# OCP2PCIe-H-F-4.net
KiCad netlist of a schematic drawn in Altium Designer
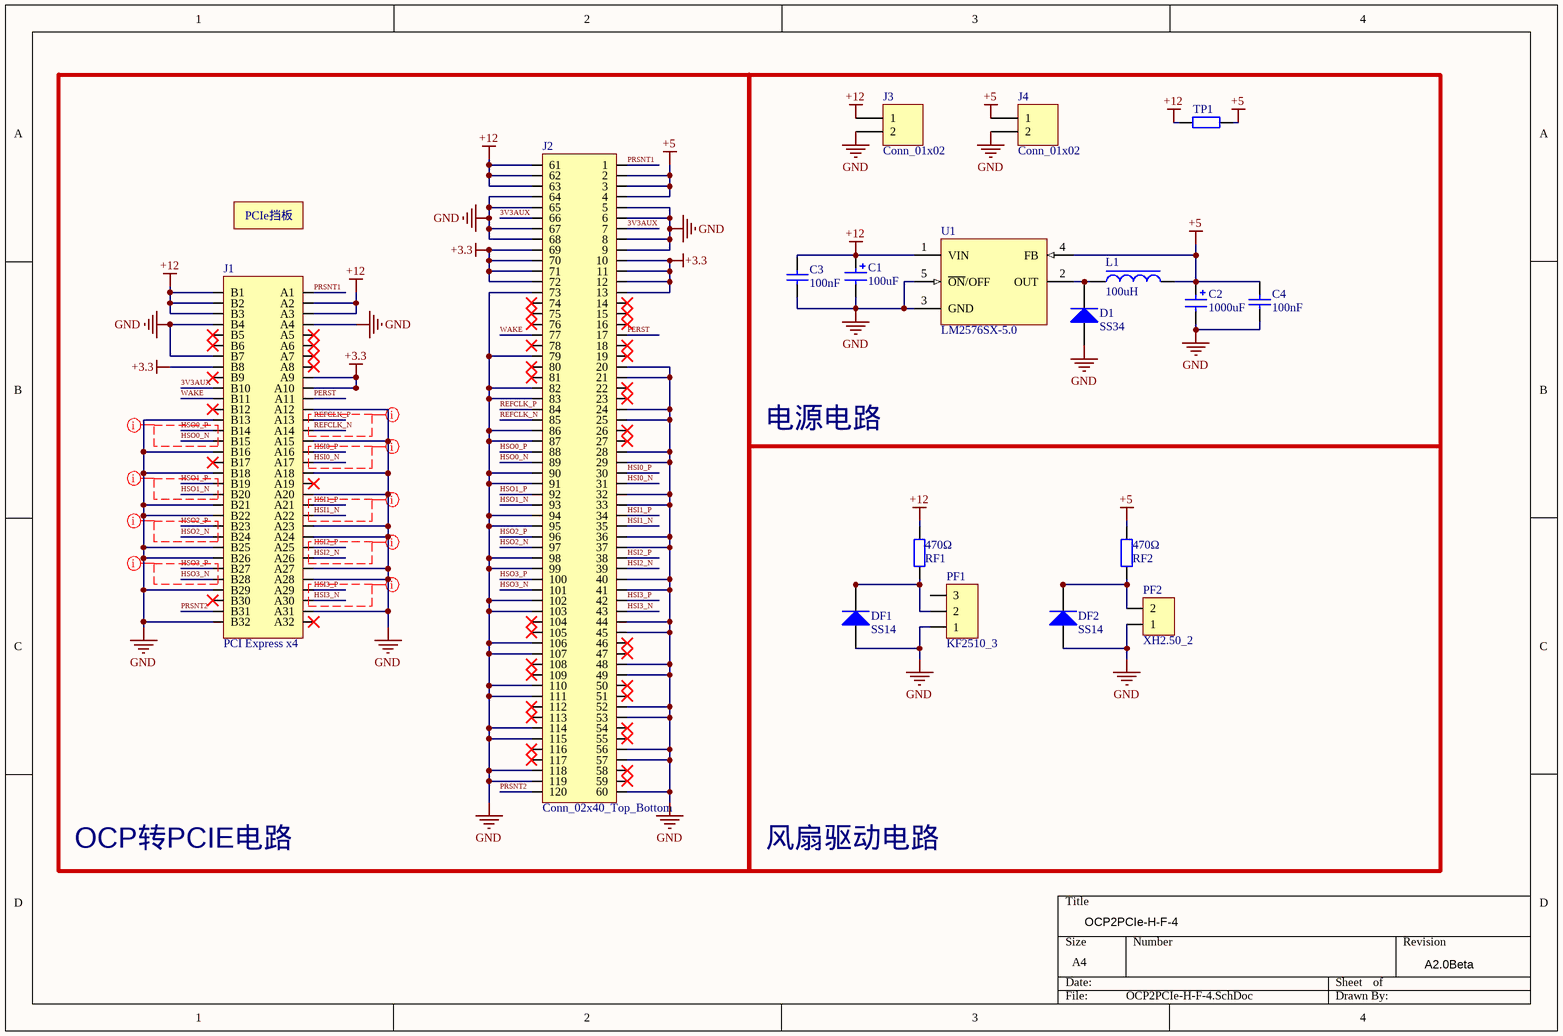
[diagram p0: OCP2PCIe-H-F-4.SchDoc]

(export (version "E")
  (design (tool "Eeschema 10.0.6"))
  (components
    (comp (ref "BEZEL")
      (value "BEZEL")
      (footprint "BEZEL")
      (description "PCIe挡板")
      (libsource (lib "OCP2PCIe-H-F-4") (part "BEZEL"))
    )
    (comp (ref "C1")
      (value "100uF")
      (footprint "CAP-SMD_BD5.0-L5.3-W5.3-FD")
      (description "贴片铝电解电容")
      (libsource (lib "OCP2PCIe") (part "7343_CP"))
    )
    (comp (ref "C2")
      (value "1000uF")
      (footprint "CAP-SMD_BD10.0-L10.3-W10.3-FD")
      (description "贴片铝电解电容")
      (libsource (lib "OCP2PCIe") (part "7343_CP"))
    )
    (comp (ref "C3")
      (value "100nF")
      (footprint "0603_C")
      (description "贴片电容")
      (libsource (lib "OCP2PCIe") (part "0805 Cap"))
    )
    (comp (ref "C4")
      (value "100nF")
      (footprint "0603_C")
      (description "贴片电容")
      (libsource (lib "OCP2PCIe") (part "0805 Cap"))
    )
    (comp (ref "D1")
      (value "SS34")
      (footprint "SMA(DO-214AC)_S1")
      (description "肖特基二极管")
      (libsource (lib "OCP2PCIe-H-F-4") (part "SMA(DO-214AC) M7"))
    )
    (comp (ref "DF1")
      (value "SS14")
      (footprint "SMA(DO-214AC)_S1")
      (description "二极管")
      (libsource (lib "OCP2PCIe-H-F-4") (part "SMA(DO-214AC) M7"))
    )
    (comp (ref "DF2")
      (value "SS14")
      (footprint "SMA(DO-214AC)_S1")
      (description "二极管")
      (libsource (lib "OCP2PCIe-H-F-4") (part "SMA(DO-214AC) M7"))
    )
    (comp (ref "J1")
      (value "PCI Express x4")
      (footprint "PCI Express x4")
      (description "插座-PCIe")
      (libsource (lib "OCP2PCIe") (part "PCI Express x4"))
    )
    (comp (ref "J2")
      (value "Conn_02x40_Top_Bottom")
      (footprint "Conn_02x40_Top_Bottom")
      (description "插座-0.8mm")
      (libsource (lib "OCP2PCIe") (part "Conn_02x40_Top_Bottom"))
    )
    (comp (ref "J3")
      (value "Conn_01x02")
      (footprint "Conn_01x02")
      (description "插座-2.54mm")
      (fields (field (name "PUBLISHER") "Altium Limited"))
      (libsource (lib "OCP2PCIe") (part "Conn_01x02"))
    )
    (comp (ref "J4")
      (value "Conn_01x02")
      (footprint "Conn_01x02")
      (description "插座-2.54mm")
      (fields (field (name "PUBLISHER") "Altium Limited"))
      (libsource (lib "OCP2PCIe") (part "Conn_01x02"))
    )
    (comp (ref "L1")
      (value "100uH")
      (footprint "SMD_5050")
      (description "贴片电感")
      (libsource (lib "OCP2PCIe-H-F-4") (part "SDM_Inductors"))
    )
    (comp (ref "PF1")
      (value "KF2510_3")
      (footprint "CONN-KF_2510_3PIN")
      (description "插座-KF2510-3")
      (fields (field (name "PUBLISHER") "Altium Limited"))
      (libsource (lib "OCP2PCIe-H-F-4") (part "Conn_KF2510_3"))
    )
    (comp (ref "PF2")
      (value "XH2.50_2")
      (footprint "CONN-TH_P2.50_2Pin")
      (description "插座-2.50mm")
      (fields (field (name "PUBLISHER") "Altium Limited"))
      (libsource (lib "OCP2PCIe-H-F-4") (part "Conn_XH2.50_2"))
    )
    (comp (ref "RF1")
      (value "470Ω")
      (footprint "1206_R")
      (description "贴片电阻")
      (libsource (lib "OCP2PCIe-H-F-4") (part "1206_R"))
    )
    (comp (ref "RF2")
      (value "470Ω")
      (footprint "1206_R")
      (description "贴片电阻")
      (libsource (lib "OCP2PCIe-H-F-4") (part "1206_R"))
    )
    (comp (ref "TP1")
      (value "0Ω")
      (footprint "0805_R")
      (description "贴片电阻")
      (libsource (lib "Miscellaneous Devices LC") (part "0805 0Ω (0R0) 1%"))
    )
    (comp (ref "U1")
      (value "LM2576SX-5.0")
      (footprint "TO-263-5")
      (description "DC-DC芯片")
      (libsource (lib "OCP2PCIe-H-F-4") (part "LM2576SX-5.0"))
    )
  )
  (nets
    (net (code "1") (name "+3.3") (class "Default")
      (node (ref "J1") (pin "A10") (pinfunction "A10_A10") (pintype "passive"))
      (node (ref "J1") (pin "A9") (pinfunction "A9_A9") (pintype "passive"))
      (node (ref "J1") (pin "B8") (pinfunction "B8_B8") (pintype "passive"))
      (node (ref "J2") (pin "10") (pinfunction "10_10") (pintype "passive"))
      (node (ref "J2") (pin "11") (pinfunction "11_11") (pintype "passive"))
      (node (ref "J2") (pin "12") (pinfunction "12_12") (pintype "passive"))
      (node (ref "J2") (pin "13") (pinfunction "13_13") (pintype "passive"))
      (node (ref "J2") (pin "69") (pinfunction "69_69") (pintype "passive"))
      (node (ref "J2") (pin "70") (pinfunction "70_70") (pintype "passive"))
      (node (ref "J2") (pin "71") (pinfunction "71_71") (pintype "passive"))
      (node (ref "J2") (pin "72") (pinfunction "72_72") (pintype "passive"))
    )
    (net (code "2") (name "+5") (class "Default")
      (node (ref "C2") (pin "1") (pinfunction "1_1") (pintype "passive"))
      (node (ref "C4") (pin "2") (pinfunction "2_2") (pintype "passive"))
      (node (ref "J2") (pin "2") (pinfunction "2_2") (pintype "passive"))
      (node (ref "J2") (pin "3") (pinfunction "3_3") (pintype "passive"))
      (node (ref "J2") (pin "4") (pinfunction "4_4") (pintype "passive"))
      (node (ref "J4") (pin "1") (pinfunction "1_1") (pintype "passive"))
      (node (ref "L1") (pin "2") (pinfunction "2_2") (pintype "passive"))
      (node (ref "RF2") (pin "2") (pinfunction "2_2") (pintype "passive"))
      (node (ref "TP1") (pin "2") (pinfunction "2_2") (pintype "passive"))
      (node (ref "U1") (pin "4") (pinfunction "FB_4") (pintype "input"))
    )
    (net (code "3") (name "+12") (class "Default")
      (node (ref "C1") (pin "1") (pinfunction "1_1") (pintype "passive"))
      (node (ref "C3") (pin "2") (pinfunction "2_2") (pintype "passive"))
      (node (ref "J1") (pin "A2") (pinfunction "A2_A2") (pintype "passive"))
      (node (ref "J1") (pin "A3") (pinfunction "A3_A3") (pintype "passive"))
      (node (ref "J1") (pin "B1") (pinfunction "B1_B1") (pintype "passive"))
      (node (ref "J1") (pin "B2") (pinfunction "B2_B2") (pintype "passive"))
      (node (ref "J1") (pin "B3") (pinfunction "B3_B3") (pintype "passive"))
      (node (ref "J2") (pin "61") (pinfunction "61_61") (pintype "passive"))
      (node (ref "J2") (pin "62") (pinfunction "62_62") (pintype "passive"))
      (node (ref "J2") (pin "63") (pinfunction "63_63") (pintype "passive"))
      (node (ref "J3") (pin "1") (pinfunction "1_1") (pintype "passive"))
      (node (ref "RF1") (pin "2") (pinfunction "2_2") (pintype "passive"))
      (node (ref "TP1") (pin "1") (pinfunction "1_1") (pintype "passive"))
      (node (ref "U1") (pin "1") (pinfunction "VIN_1") (pintype "power_in"))
    )
    (net (code "4") (name "/3V3AUX") (class "Default")
      (node (ref "J1") (pin "B10") (pinfunction "B10_B10") (pintype "passive"))
      (node (ref "J2") (pin "66") (pinfunction "66_66") (pintype "passive"))
      (node (ref "J2") (pin "7") (pinfunction "7_7") (pintype "passive"))
    )
    (net (code "5") (name "/HSI0_N") (class "Default")
      (node (ref "J1") (pin "A17") (pinfunction "A17_A17") (pintype "passive"))
      (node (ref "J2") (pin "31") (pinfunction "31_31") (pintype "passive"))
    )
    (net (code "6") (name "/HSI0_P") (class "Default")
      (node (ref "J1") (pin "A16") (pinfunction "A16_A16") (pintype "passive"))
      (node (ref "J2") (pin "30") (pinfunction "30_30") (pintype "passive"))
    )
    (net (code "7") (name "/HSI1_N") (class "Default")
      (node (ref "J1") (pin "A22") (pinfunction "A22_A22") (pintype "passive"))
      (node (ref "J2") (pin "35") (pinfunction "35_35") (pintype "passive"))
    )
    (net (code "8") (name "/HSI1_P") (class "Default")
      (node (ref "J1") (pin "A21") (pinfunction "A21_A21") (pintype "passive"))
      (node (ref "J2") (pin "34") (pinfunction "34_34") (pintype "passive"))
    )
    (net (code "9") (name "/HSI2_N") (class "Default")
      (node (ref "J1") (pin "A26") (pinfunction "A26_A26") (pintype "passive"))
      (node (ref "J2") (pin "39") (pinfunction "39_39") (pintype "passive"))
    )
    (net (code "10") (name "/HSI2_P") (class "Default")
      (node (ref "J1") (pin "A25") (pinfunction "A25_A25") (pintype "passive"))
      (node (ref "J2") (pin "38") (pinfunction "38_38") (pintype "passive"))
    )
    (net (code "11") (name "/HSI3_N") (class "Default")
      (node (ref "J1") (pin "A30") (pinfunction "A30_A30") (pintype "passive"))
      (node (ref "J2") (pin "43") (pinfunction "43_43") (pintype "passive"))
    )
    (net (code "12") (name "/HSI3_P") (class "Default")
      (node (ref "J1") (pin "A29") (pinfunction "A29_A29") (pintype "passive"))
      (node (ref "J2") (pin "42") (pinfunction "42_42") (pintype "passive"))
    )
    (net (code "13") (name "/HSO0_N") (class "Default")
      (node (ref "J1") (pin "B15") (pinfunction "B15_B15") (pintype "passive"))
      (node (ref "J2") (pin "89") (pinfunction "89_89") (pintype "passive"))
    )
    (net (code "14") (name "/HSO0_P") (class "Default")
      (node (ref "J1") (pin "B14") (pinfunction "B14_B14") (pintype "passive"))
      (node (ref "J2") (pin "88") (pinfunction "88_88") (pintype "passive"))
    )
    (net (code "15") (name "/HSO1_N") (class "Default")
      (node (ref "J1") (pin "B20") (pinfunction "B20_B20") (pintype "passive"))
      (node (ref "J2") (pin "93") (pinfunction "93_93") (pintype "passive"))
    )
    (net (code "16") (name "/HSO1_P") (class "Default")
      (node (ref "J1") (pin "B19") (pinfunction "B19_B19") (pintype "passive"))
      (node (ref "J2") (pin "92") (pinfunction "92_92") (pintype "passive"))
    )
    (net (code "17") (name "/HSO2_N") (class "Default")
      (node (ref "J1") (pin "B24") (pinfunction "B24_B24") (pintype "passive"))
      (node (ref "J2") (pin "97") (pinfunction "97_97") (pintype "passive"))
    )
    (net (code "18") (name "/HSO2_P") (class "Default")
      (node (ref "J1") (pin "B23") (pinfunction "B23_B23") (pintype "passive"))
      (node (ref "J2") (pin "96") (pinfunction "96_96") (pintype "passive"))
    )
    (net (code "19") (name "/HSO3_N") (class "Default")
      (node (ref "J1") (pin "B28") (pinfunction "B28_B28") (pintype "passive"))
      (node (ref "J2") (pin "101") (pinfunction "101_101") (pintype "passive"))
    )
    (net (code "20") (name "/HSO3_P") (class "Default")
      (node (ref "J1") (pin "B27") (pinfunction "B27_B27") (pintype "passive"))
      (node (ref "J2") (pin "100") (pinfunction "100_100") (pintype "passive"))
    )
    (net (code "21") (name "/PERST") (class "Default")
      (node (ref "J1") (pin "A11") (pinfunction "A11_A11") (pintype "passive"))
      (node (ref "J2") (pin "17") (pinfunction "17_17") (pintype "passive"))
    )
    (net (code "22") (name "/PRSNT1") (class "Default")
      (node (ref "J1") (pin "A1") (pinfunction "A1_A1") (pintype "passive"))
      (node (ref "J2") (pin "1") (pinfunction "1_1") (pintype "passive"))
    )
    (net (code "23") (name "/PRSNT2") (class "Default")
      (node (ref "J1") (pin "B31") (pinfunction "B31_B31") (pintype "passive"))
      (node (ref "J2") (pin "120") (pinfunction "120_120") (pintype "passive"))
    )
    (net (code "24") (name "/REFCLK_N") (class "Default")
      (node (ref "J1") (pin "A14") (pinfunction "A14_A14") (pintype "passive"))
      (node (ref "J2") (pin "85") (pinfunction "85_85") (pintype "passive"))
    )
    (net (code "25") (name "/REFCLK_P") (class "Default")
      (node (ref "J1") (pin "A13") (pinfunction "A13_A13") (pintype "passive"))
      (node (ref "J2") (pin "84") (pinfunction "84_84") (pintype "passive"))
    )
    (net (code "26") (name "/WAKE") (class "Default")
      (node (ref "J1") (pin "B11") (pinfunction "B11_B11") (pintype "passive"))
      (node (ref "J2") (pin "77") (pinfunction "77_77") (pintype "passive"))
    )
    (net (code "27") (name "GND") (class "Default")
      (node (ref "C1") (pin "2") (pinfunction "2_2") (pintype "passive"))
      (node (ref "C2") (pin "2") (pinfunction "2_2") (pintype "passive"))
      (node (ref "C3") (pin "1") (pinfunction "1_1") (pintype "passive"))
      (node (ref "C4") (pin "1") (pinfunction "1_1") (pintype "passive"))
      (node (ref "D1") (pin "1") (pinfunction "A_1") (pintype "passive"))
      (node (ref "DF1") (pin "1") (pinfunction "A_1") (pintype "passive"))
      (node (ref "DF2") (pin "1") (pinfunction "A_1") (pintype "passive"))
      (node (ref "J1") (pin "A12") (pinfunction "A12_A12") (pintype "passive"))
      (node (ref "J1") (pin "A15") (pinfunction "A15_A15") (pintype "passive"))
      (node (ref "J1") (pin "A18") (pinfunction "A18_A18") (pintype "passive"))
      (node (ref "J1") (pin "A20") (pinfunction "A20_A20") (pintype "passive"))
      (node (ref "J1") (pin "A23") (pinfunction "A23_A23") (pintype "passive"))
      (node (ref "J1") (pin "A24") (pinfunction "A24_A24") (pintype "passive"))
      (node (ref "J1") (pin "A27") (pinfunction "A27_A27") (pintype "passive"))
      (node (ref "J1") (pin "A28") (pinfunction "A28_A28") (pintype "passive"))
      (node (ref "J1") (pin "A31") (pinfunction "A31_A31") (pintype "passive"))
      (node (ref "J1") (pin "A4") (pinfunction "A4_A4") (pintype "passive"))
      (node (ref "J1") (pin "B13") (pinfunction "B13_B13") (pintype "passive"))
      (node (ref "J1") (pin "B16") (pinfunction "B16_B16") (pintype "passive"))
      (node (ref "J1") (pin "B18") (pinfunction "B18_B18") (pintype "passive"))
      (node (ref "J1") (pin "B21") (pinfunction "B21_B21") (pintype "passive"))
      (node (ref "J1") (pin "B22") (pinfunction "B22_B22") (pintype "passive"))
      (node (ref "J1") (pin "B25") (pinfunction "B25_B25") (pintype "passive"))
      (node (ref "J1") (pin "B26") (pinfunction "B26_B26") (pintype "passive"))
      (node (ref "J1") (pin "B29") (pinfunction "B29_B29") (pintype "passive"))
      (node (ref "J1") (pin "B32") (pinfunction "B32_B32") (pintype "passive"))
      (node (ref "J1") (pin "B4") (pinfunction "B4_B4") (pintype "passive"))
      (node (ref "J1") (pin "B7") (pinfunction "B7_B7") (pintype "passive"))
      (node (ref "J2") (pin "102") (pinfunction "102_102") (pintype "passive"))
      (node (ref "J2") (pin "103") (pinfunction "103_103") (pintype "passive"))
      (node (ref "J2") (pin "106") (pinfunction "106_106") (pintype "passive"))
      (node (ref "J2") (pin "107") (pinfunction "107_107") (pintype "passive"))
      (node (ref "J2") (pin "110") (pinfunction "110_110") (pintype "passive"))
      (node (ref "J2") (pin "111") (pinfunction "111_111") (pintype "passive"))
      (node (ref "J2") (pin "114") (pinfunction "114_114") (pintype "passive"))
      (node (ref "J2") (pin "115") (pinfunction "115_115") (pintype "passive"))
      (node (ref "J2") (pin "118") (pinfunction "118_118") (pintype "passive"))
      (node (ref "J2") (pin "119") (pinfunction "119_119") (pintype "passive"))
      (node (ref "J2") (pin "20") (pinfunction "20_20") (pintype "passive"))
      (node (ref "J2") (pin "21") (pinfunction "21_21") (pintype "passive"))
      (node (ref "J2") (pin "24") (pinfunction "24_24") (pintype "passive"))
      (node (ref "J2") (pin "25") (pinfunction "25_25") (pintype "passive"))
      (node (ref "J2") (pin "28") (pinfunction "28_28") (pintype "passive"))
      (node (ref "J2") (pin "29") (pinfunction "29_29") (pintype "passive"))
      (node (ref "J2") (pin "32") (pinfunction "32_32") (pintype "passive"))
      (node (ref "J2") (pin "33") (pinfunction "33_33") (pintype "passive"))
      (node (ref "J2") (pin "36") (pinfunction "36_36") (pintype "passive"))
      (node (ref "J2") (pin "37") (pinfunction "37_37") (pintype "passive"))
      (node (ref "J2") (pin "40") (pinfunction "40_40") (pintype "passive"))
      (node (ref "J2") (pin "41") (pinfunction "41_41") (pintype "passive"))
      (node (ref "J2") (pin "44") (pinfunction "44_44") (pintype "passive"))
      (node (ref "J2") (pin "45") (pinfunction "45_45") (pintype "passive"))
      (node (ref "J2") (pin "48") (pinfunction "48_48") (pintype "passive"))
      (node (ref "J2") (pin "49") (pinfunction "49_49") (pintype "passive"))
      (node (ref "J2") (pin "5") (pinfunction "5_5") (pintype "passive"))
      (node (ref "J2") (pin "52") (pinfunction "52_52") (pintype "passive"))
      (node (ref "J2") (pin "53") (pinfunction "53_53") (pintype "passive"))
      (node (ref "J2") (pin "56") (pinfunction "56_56") (pintype "passive"))
      (node (ref "J2") (pin "57") (pinfunction "57_57") (pintype "passive"))
      (node (ref "J2") (pin "6") (pinfunction "6_6") (pintype "passive"))
      (node (ref "J2") (pin "60") (pinfunction "60_60") (pintype "passive"))
      (node (ref "J2") (pin "64") (pinfunction "64_64") (pintype "passive"))
      (node (ref "J2") (pin "65") (pinfunction "65_65") (pintype "passive"))
      (node (ref "J2") (pin "67") (pinfunction "67_67") (pintype "passive"))
      (node (ref "J2") (pin "68") (pinfunction "68_68") (pintype "passive"))
      (node (ref "J2") (pin "73") (pinfunction "73_73") (pintype "passive"))
      (node (ref "J2") (pin "79") (pinfunction "79_79") (pintype "passive"))
      (node (ref "J2") (pin "8") (pinfunction "8_8") (pintype "passive"))
      (node (ref "J2") (pin "82") (pinfunction "82_82") (pintype "passive"))
      (node (ref "J2") (pin "83") (pinfunction "83_83") (pintype "passive"))
      (node (ref "J2") (pin "86") (pinfunction "86_86") (pintype "passive"))
      (node (ref "J2") (pin "87") (pinfunction "87_87") (pintype "passive"))
      (node (ref "J2") (pin "9") (pinfunction "9_9") (pintype "passive"))
      (node (ref "J2") (pin "90") (pinfunction "90_90") (pintype "passive"))
      (node (ref "J2") (pin "91") (pinfunction "91_91") (pintype "passive"))
      (node (ref "J2") (pin "94") (pinfunction "94_94") (pintype "passive"))
      (node (ref "J2") (pin "95") (pinfunction "95_95") (pintype "passive"))
      (node (ref "J2") (pin "98") (pinfunction "98_98") (pintype "passive"))
      (node (ref "J2") (pin "99") (pinfunction "99_99") (pintype "passive"))
      (node (ref "J3") (pin "2") (pinfunction "2_2") (pintype "passive"))
      (node (ref "J4") (pin "2") (pinfunction "2_2") (pintype "passive"))
      (node (ref "PF1") (pin "1") (pinfunction "1_1") (pintype "passive"))
      (node (ref "PF2") (pin "1") (pinfunction "1_1") (pintype "passive"))
      (node (ref "U1") (pin "0") (pinfunction "GND_0") (pintype "power_in"))
      (node (ref "U1") (pin "3") (pinfunction "GND_3") (pintype "power_in"))
      (node (ref "U1") (pin "5") (pinfunction "~{ON}/OFF_5") (pintype "input"))
    )
    (net (code "28") (name "Net-(D1-K)") (class "Default")
      (node (ref "D1") (pin "2") (pinfunction "K_2") (pintype "passive"))
      (node (ref "L1") (pin "1") (pinfunction "1_1") (pintype "passive"))
      (node (ref "U1") (pin "2") (pinfunction "OUT_2") (pintype "power_in"))
    )
    (net (code "29") (name "Net-(DF1-K)") (class "Default")
      (node (ref "DF1") (pin "2") (pinfunction "K_2") (pintype "passive"))
      (node (ref "PF1") (pin "2") (pinfunction "2_2") (pintype "passive"))
      (node (ref "RF1") (pin "1") (pinfunction "1_1") (pintype "passive"))
    )
    (net (code "30") (name "Net-(DF2-K)") (class "Default")
      (node (ref "DF2") (pin "2") (pinfunction "K_2") (pintype "passive"))
      (node (ref "PF2") (pin "2") (pinfunction "2_2") (pintype "passive"))
      (node (ref "RF2") (pin "1") (pinfunction "1_1") (pintype "passive"))
    )
    (net (code "31") (name "unconnected-(J1-PadA5)") (class "Default")
      (node (ref "J1") (pin "A5") (pinfunction "A5_A5") (pintype "passive+no_connect"))
    )
    (net (code "32") (name "unconnected-(J1-PadA6)") (class "Default")
      (node (ref "J1") (pin "A6") (pinfunction "A6_A6") (pintype "passive+no_connect"))
    )
    (net (code "33") (name "unconnected-(J1-PadA7)") (class "Default")
      (node (ref "J1") (pin "A7") (pinfunction "A7_A7") (pintype "passive+no_connect"))
    )
    (net (code "34") (name "unconnected-(J1-PadA8)") (class "Default")
      (node (ref "J1") (pin "A8") (pinfunction "A8_A8") (pintype "passive+no_connect"))
    )
    (net (code "35") (name "unconnected-(J1-PadA19)") (class "Default")
      (node (ref "J1") (pin "A19") (pinfunction "A19_A19") (pintype "passive+no_connect"))
    )
    (net (code "36") (name "unconnected-(J1-PadA32)") (class "Default")
      (node (ref "J1") (pin "A32") (pinfunction "A32_A32") (pintype "passive+no_connect"))
    )
    (net (code "37") (name "unconnected-(J1-PadB5)") (class "Default")
      (node (ref "J1") (pin "B5") (pinfunction "B5_B5") (pintype "passive+no_connect"))
    )
    (net (code "38") (name "unconnected-(J1-PadB6)") (class "Default")
      (node (ref "J1") (pin "B6") (pinfunction "B6_B6") (pintype "passive+no_connect"))
    )
    (net (code "39") (name "unconnected-(J1-PadB9)") (class "Default")
      (node (ref "J1") (pin "B9") (pinfunction "B9_B9") (pintype "passive+no_connect"))
    )
    (net (code "40") (name "unconnected-(J1-PadB12)") (class "Default")
      (node (ref "J1") (pin "B12") (pinfunction "B12_B12") (pintype "passive+no_connect"))
    )
    (net (code "41") (name "unconnected-(J1-PadB17)") (class "Default")
      (node (ref "J1") (pin "B17") (pinfunction "B17_B17") (pintype "passive+no_connect"))
    )
    (net (code "42") (name "unconnected-(J1-PadB30)") (class "Default")
      (node (ref "J1") (pin "B30") (pinfunction "B30_B30") (pintype "passive+no_connect"))
    )
    (net (code "43") (name "unconnected-(J2-Pad14)") (class "Default")
      (node (ref "J2") (pin "14") (pinfunction "14_14") (pintype "passive+no_connect"))
    )
    (net (code "44") (name "unconnected-(J2-Pad15)") (class "Default")
      (node (ref "J2") (pin "15") (pinfunction "15_15") (pintype "passive+no_connect"))
    )
    (net (code "45") (name "unconnected-(J2-Pad16)") (class "Default")
      (node (ref "J2") (pin "16") (pinfunction "16_16") (pintype "passive+no_connect"))
    )
    (net (code "46") (name "unconnected-(J2-Pad18)") (class "Default")
      (node (ref "J2") (pin "18") (pinfunction "18_18") (pintype "passive+no_connect"))
    )
    (net (code "47") (name "unconnected-(J2-Pad19)") (class "Default")
      (node (ref "J2") (pin "19") (pinfunction "19_19") (pintype "passive+no_connect"))
    )
    (net (code "48") (name "unconnected-(J2-Pad22)") (class "Default")
      (node (ref "J2") (pin "22") (pinfunction "22_22") (pintype "passive+no_connect"))
    )
    (net (code "49") (name "unconnected-(J2-Pad23)") (class "Default")
      (node (ref "J2") (pin "23") (pinfunction "23_23") (pintype "passive+no_connect"))
    )
    (net (code "50") (name "unconnected-(J2-Pad26)") (class "Default")
      (node (ref "J2") (pin "26") (pinfunction "26_26") (pintype "passive+no_connect"))
    )
    (net (code "51") (name "unconnected-(J2-Pad27)") (class "Default")
      (node (ref "J2") (pin "27") (pinfunction "27_27") (pintype "passive+no_connect"))
    )
    (net (code "52") (name "unconnected-(J2-Pad46)") (class "Default")
      (node (ref "J2") (pin "46") (pinfunction "46_46") (pintype "passive+no_connect"))
    )
    (net (code "53") (name "unconnected-(J2-Pad47)") (class "Default")
      (node (ref "J2") (pin "47") (pinfunction "47_47") (pintype "passive+no_connect"))
    )
    (net (code "54") (name "unconnected-(J2-Pad50)") (class "Default")
      (node (ref "J2") (pin "50") (pinfunction "50_50") (pintype "passive+no_connect"))
    )
    (net (code "55") (name "unconnected-(J2-Pad51)") (class "Default")
      (node (ref "J2") (pin "51") (pinfunction "51_51") (pintype "passive+no_connect"))
    )
    (net (code "56") (name "unconnected-(J2-Pad54)") (class "Default")
      (node (ref "J2") (pin "54") (pinfunction "54_54") (pintype "passive+no_connect"))
    )
    (net (code "57") (name "unconnected-(J2-Pad55)") (class "Default")
      (node (ref "J2") (pin "55") (pinfunction "55_55") (pintype "passive+no_connect"))
    )
    (net (code "58") (name "unconnected-(J2-Pad58)") (class "Default")
      (node (ref "J2") (pin "58") (pinfunction "58_58") (pintype "passive+no_connect"))
    )
    (net (code "59") (name "unconnected-(J2-Pad59)") (class "Default")
      (node (ref "J2") (pin "59") (pinfunction "59_59") (pintype "passive+no_connect"))
    )
    (net (code "60") (name "unconnected-(J2-Pad74)") (class "Default")
      (node (ref "J2") (pin "74") (pinfunction "74_74") (pintype "passive+no_connect"))
    )
    (net (code "61") (name "unconnected-(J2-Pad75)") (class "Default")
      (node (ref "J2") (pin "75") (pinfunction "75_75") (pintype "passive+no_connect"))
    )
    (net (code "62") (name "unconnected-(J2-Pad76)") (class "Default")
      (node (ref "J2") (pin "76") (pinfunction "76_76") (pintype "passive+no_connect"))
    )
    (net (code "63") (name "unconnected-(J2-Pad78)") (class "Default")
      (node (ref "J2") (pin "78") (pinfunction "78_78") (pintype "passive+no_connect"))
    )
    (net (code "64") (name "unconnected-(J2-Pad80)") (class "Default")
      (node (ref "J2") (pin "80") (pinfunction "80_80") (pintype "passive+no_connect"))
    )
    (net (code "65") (name "unconnected-(J2-Pad81)") (class "Default")
      (node (ref "J2") (pin "81") (pinfunction "81_81") (pintype "passive+no_connect"))
    )
    (net (code "66") (name "unconnected-(J2-Pad104)") (class "Default")
      (node (ref "J2") (pin "104") (pinfunction "104_104") (pintype "passive+no_connect"))
    )
    (net (code "67") (name "unconnected-(J2-Pad105)") (class "Default")
      (node (ref "J2") (pin "105") (pinfunction "105_105") (pintype "passive+no_connect"))
    )
    (net (code "68") (name "unconnected-(J2-Pad108)") (class "Default")
      (node (ref "J2") (pin "108") (pinfunction "108_108") (pintype "passive+no_connect"))
    )
    (net (code "69") (name "unconnected-(J2-Pad109)") (class "Default")
      (node (ref "J2") (pin "109") (pinfunction "109_109") (pintype "passive+no_connect"))
    )
    (net (code "70") (name "unconnected-(J2-Pad112)") (class "Default")
      (node (ref "J2") (pin "112") (pinfunction "112_112") (pintype "passive+no_connect"))
    )
    (net (code "71") (name "unconnected-(J2-Pad113)") (class "Default")
      (node (ref "J2") (pin "113") (pinfunction "113_113") (pintype "passive+no_connect"))
    )
    (net (code "72") (name "unconnected-(J2-Pad116)") (class "Default")
      (node (ref "J2") (pin "116") (pinfunction "116_116") (pintype "passive+no_connect"))
    )
    (net (code "73") (name "unconnected-(J2-Pad117)") (class "Default")
      (node (ref "J2") (pin "117") (pinfunction "117_117") (pintype "passive+no_connect"))
    )
    (net (code "74") (name "unconnected-(PF1-Pad3)") (class "Default")
      (node (ref "PF1") (pin "3") (pinfunction "3_3") (pintype "passive"))
    )
  )
)
